# Sheet1.net
KiCad netlist of a schematic drawn in Altium Designer
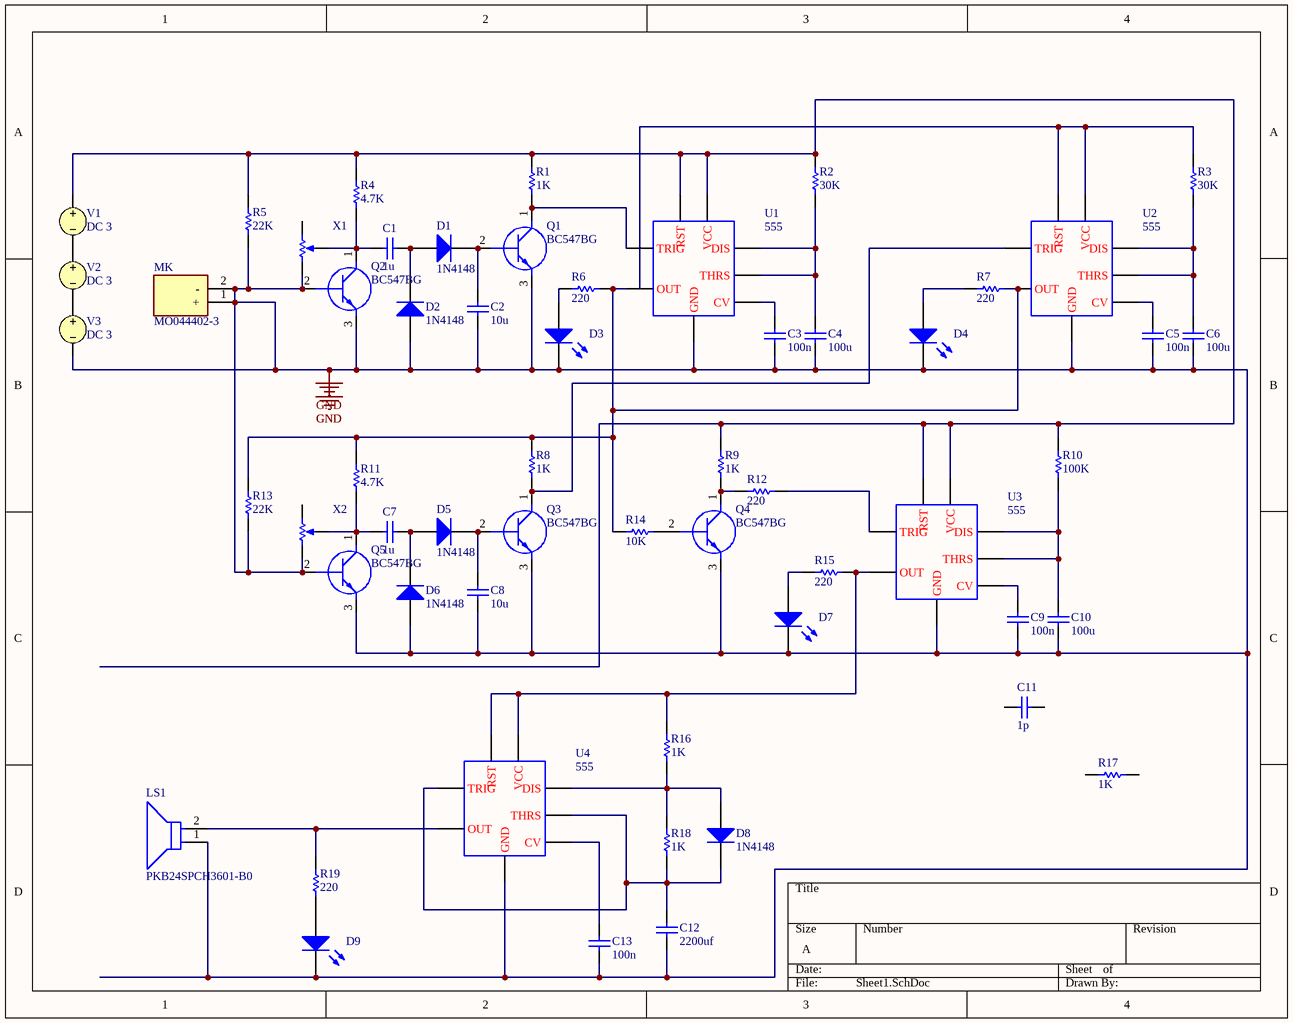
[diagram p0: Sheet1.SchDoc]

(export (version "E")
  (design (tool "Eeschema 10.0.6"))
  (components
    (comp (ref "C1")
      (value "1u")
      (description "Capacitor")
      (libsource (lib "Simulation Generic Components") (part "Capacitor"))
    )
    (comp (ref "C2")
      (value "10u")
      (description "Capacitor")
      (libsource (lib "Simulation Generic Components") (part "Capacitor"))
    )
    (comp (ref "C3")
      (value "100n")
      (description "Capacitor")
      (libsource (lib "Simulation Generic Components") (part "Capacitor"))
    )
    (comp (ref "C4")
      (value "100u")
      (description "Capacitor")
      (libsource (lib "Simulation Generic Components") (part "Capacitor"))
    )
    (comp (ref "C5")
      (value "100n")
      (description "Capacitor")
      (libsource (lib "Simulation Generic Components") (part "Capacitor"))
    )
    (comp (ref "C6")
      (value "100u")
      (description "Capacitor")
      (libsource (lib "Simulation Generic Components") (part "Capacitor"))
    )
    (comp (ref "C7")
      (value "1u")
      (description "Capacitor")
      (libsource (lib "Simulation Generic Components") (part "Capacitor"))
    )
    (comp (ref "C8")
      (value "10u")
      (description "Capacitor")
      (libsource (lib "Simulation Generic Components") (part "Capacitor"))
    )
    (comp (ref "C9")
      (value "100n")
      (description "Capacitor")
      (libsource (lib "Simulation Generic Components") (part "Capacitor"))
    )
    (comp (ref "C10")
      (value "100u")
      (description "Capacitor")
      (libsource (lib "Simulation Generic Components") (part "Capacitor"))
    )
    (comp (ref "C11")
      (value "1p")
      (description "Capacitor")
      (libsource (lib "Simulation Generic Components") (part "Capacitor"))
    )
    (comp (ref "C12")
      (value "2200uf")
      (description "Capacitor")
      (libsource (lib "Simulation Generic Components") (part "Capacitor"))
    )
    (comp (ref "C13")
      (value "100n")
      (description "Capacitor")
      (libsource (lib "Simulation Generic Components") (part "Capacitor"))
    )
    (comp (ref "D1")
      (value "1N4148")
      (footprint "NXP-SOD27-2_V")
      (description "High-speed Diode, 100 V, 450 mA, 2-Pin SOD27, RoHS")
      (fields (field (name "MANUFACTURER") "NXP Semiconductors"))
      (libsource (lib "Altium Content Vault") (part "NXP-A1K2-2"))
    )
    (comp (ref "D2")
      (value "1N4148")
      (footprint "NXP-SOD27-2_V")
      (description "High-speed Diode, 100 V, 450 mA, 2-Pin SOD27, RoHS")
      (fields (field (name "MANUFACTURER") "NXP Semiconductors"))
      (libsource (lib "Altium Content Vault") (part "NXP-A1K2-2"))
    )
    (comp (ref "D3")
      (value "Light-Emitting Diode")
      (libsource (lib "Simulation Generic Components") (part "LED"))
    )
    (comp (ref "D4")
      (value "Light-Emitting Diode")
      (libsource (lib "Simulation Generic Components") (part "LED"))
    )
    (comp (ref "D5")
      (value "1N4148")
      (footprint "NXP-SOD27-2_V")
      (description "High-speed Diode, 100 V, 450 mA, 2-Pin SOD27, RoHS")
      (fields (field (name "MANUFACTURER") "NXP Semiconductors"))
      (libsource (lib "Altium Content Vault") (part "NXP-A1K2-2"))
    )
    (comp (ref "D6")
      (value "1N4148")
      (footprint "NXP-SOD27-2_V")
      (description "High-speed Diode, 100 V, 450 mA, 2-Pin SOD27, RoHS")
      (fields (field (name "MANUFACTURER") "NXP Semiconductors"))
      (libsource (lib "Altium Content Vault") (part "NXP-A1K2-2"))
    )
    (comp (ref "D7")
      (value "Light-Emitting Diode")
      (libsource (lib "Simulation Generic Components") (part "LED"))
    )
    (comp (ref "D8")
      (value "1N4148")
      (footprint "NXP-SOD27-2_V")
      (description "High-speed Diode, 100 V, 450 mA, 2-Pin SOD27, RoHS")
      (fields (field (name "MANUFACTURER") "NXP Semiconductors"))
      (libsource (lib "Altium Content Vault") (part "NXP-A1K2-2"))
    )
    (comp (ref "D9")
      (value "Light-Emitting Diode")
      (libsource (lib "Simulation Generic Components") (part "LED"))
    )
    (comp (ref "LS1")
      (value "PKB24SPCH3601-B0")
      (footprint "FP-PKB24SPCH3601-B0-MFG")
      (description "AUDIO PIEZO TRANSDUCER 3-15V TH")
      (libsource (lib "Altium Content Vault") (part "1973c4b650225fd2ddacaff6b763965"))
    )
    (comp (ref "MK")
      (value "MO044402-3")
      (footprint "SamacSys:MO0444023")
      (description "Microphone")
      (fields (field (name "MOUSER PART NUMBER") "497-MO044402-3"))
      (libsource (lib "*") (part "MO044402-3"))
    )
    (comp (ref "Q1")
      (value "BC547BG")
      (footprint "SamacSys:BC547BG")
      (description "Transistor BJT NPN")
      (libsource (lib "*") (part "BC547BG"))
    )
    (comp (ref "Q2")
      (value "BC547BG")
      (footprint "SamacSys:BC547BG")
      (description "Transistor BJT NPN")
      (libsource (lib "*") (part "BC547BG"))
    )
    (comp (ref "Q3")
      (value "BC547BG")
      (footprint "SamacSys:BC547BG")
      (description "Transistor BJT NPN")
      (libsource (lib "*") (part "BC547BG"))
    )
    (comp (ref "Q4")
      (value "BC547BG")
      (footprint "SamacSys:BC547BG")
      (description "Transistor BJT NPN")
      (libsource (lib "*") (part "BC547BG"))
    )
    (comp (ref "Q5")
      (value "BC547BG")
      (footprint "SamacSys:BC547BG")
      (description "Transistor BJT NPN")
      (libsource (lib "*") (part "BC547BG"))
    )
    (comp (ref "R1")
      (value "1K")
      (description "Resistor")
      (libsource (lib "Simulation Generic Components") (part "Resistor"))
    )
    (comp (ref "R2")
      (value "30K")
      (description "Resistor")
      (libsource (lib "Simulation Generic Components") (part "Resistor"))
    )
    (comp (ref "R3")
      (value "30K")
      (description "Resistor")
      (libsource (lib "Simulation Generic Components") (part "Resistor"))
    )
    (comp (ref "R4")
      (value "4.7K")
      (description "Resistor")
      (libsource (lib "Simulation Generic Components") (part "Resistor"))
    )
    (comp (ref "R5")
      (value "22K")
      (description "Resistor")
      (libsource (lib "Simulation Generic Components") (part "Resistor"))
    )
    (comp (ref "R6")
      (value "220")
      (description "Resistor")
      (libsource (lib "Simulation Generic Components") (part "Resistor"))
    )
    (comp (ref "R7")
      (value "220")
      (description "Resistor")
      (libsource (lib "Simulation Generic Components") (part "Resistor"))
    )
    (comp (ref "R8")
      (value "1K")
      (description "Resistor")
      (libsource (lib "Simulation Generic Components") (part "Resistor"))
    )
    (comp (ref "R9")
      (value "1K")
      (description "Resistor")
      (libsource (lib "Simulation Generic Components") (part "Resistor"))
    )
    (comp (ref "R10")
      (value "100K")
      (description "Resistor")
      (libsource (lib "Simulation Generic Components") (part "Resistor"))
    )
    (comp (ref "R11")
      (value "4.7K")
      (description "Resistor")
      (libsource (lib "Simulation Generic Components") (part "Resistor"))
    )
    (comp (ref "R12")
      (value "220")
      (description "Resistor")
      (libsource (lib "Simulation Generic Components") (part "Resistor"))
    )
    (comp (ref "R13")
      (value "22K")
      (description "Resistor")
      (libsource (lib "Simulation Generic Components") (part "Resistor"))
    )
    (comp (ref "R14")
      (value "10K")
      (description "Resistor")
      (libsource (lib "Simulation Generic Components") (part "Resistor"))
    )
    (comp (ref "R15")
      (value "220")
      (description "Resistor")
      (libsource (lib "Simulation Generic Components") (part "Resistor"))
    )
    (comp (ref "R16")
      (value "1K")
      (description "Resistor")
      (libsource (lib "Simulation Generic Components") (part "Resistor"))
    )
    (comp (ref "R17")
      (value "1K")
      (description "Resistor")
      (libsource (lib "Simulation Generic Components") (part "Resistor"))
    )
    (comp (ref "R18")
      (value "1K")
      (description "Resistor")
      (libsource (lib "Simulation Generic Components") (part "Resistor"))
    )
    (comp (ref "R19")
      (value "220")
      (description "Resistor")
      (libsource (lib "Simulation Generic Components") (part "Resistor"))
    )
    (comp (ref "U1")
      (value "555")
      (description "Timer 555")
      (libsource (lib "Simulation Generic Components") (part "555"))
    )
    (comp (ref "U2")
      (value "555")
      (description "Timer 555")
      (libsource (lib "Simulation Generic Components") (part "555"))
    )
    (comp (ref "U3")
      (value "555")
      (description "Timer 555")
      (libsource (lib "Simulation Generic Components") (part "555"))
    )
    (comp (ref "U4")
      (value "555")
      (description "Timer 555")
      (libsource (lib "Simulation Generic Components") (part "555"))
    )
    (comp (ref "V1")
      (value "DC 3")
      (description "Voltage Source")
      (fields (field (name "PUBLISHER") "Altium Limited"))
      (libsource (lib "Simulation Generic Components") (part "VSRC"))
    )
    (comp (ref "V2")
      (value "DC 3")
      (description "Voltage Source")
      (fields (field (name "PUBLISHER") "Altium Limited"))
      (libsource (lib "Simulation Generic Components") (part "VSRC"))
    )
    (comp (ref "V3")
      (value "DC 3")
      (description "Voltage Source")
      (fields (field (name "PUBLISHER") "Altium Limited"))
      (libsource (lib "Simulation Generic Components") (part "VSRC"))
    )
    (comp (ref "X1")
      (value "Potentiometer")
      (libsource (lib "Simulation Generic Components") (part "Potentiometer"))
    )
    (comp (ref "X2")
      (value "Potentiometer")
      (libsource (lib "Simulation Generic Components") (part "Potentiometer"))
    )
  )
  (nets
    (net (code "1") (name "GND") (class "Default")
      (node (ref "C10") (pin "1") (pinfunction "1_1") (pintype "passive"))
      (node (ref "C12") (pin "1") (pinfunction "1_1") (pintype "passive"))
      (node (ref "C13") (pin "1") (pinfunction "1_1") (pintype "passive"))
      (node (ref "C2") (pin "1") (pinfunction "1_1") (pintype "passive"))
      (node (ref "C3") (pin "1") (pinfunction "1_1") (pintype "passive"))
      (node (ref "C4") (pin "1") (pinfunction "1_1") (pintype "passive"))
      (node (ref "C5") (pin "1") (pinfunction "1_1") (pintype "passive"))
      (node (ref "C6") (pin "1") (pinfunction "1_1") (pintype "passive"))
      (node (ref "C8") (pin "1") (pinfunction "1_1") (pintype "passive"))
      (node (ref "C9") (pin "1") (pinfunction "1_1") (pintype "passive"))
      (node (ref "D2") (pin "1") (pinfunction "A_1") (pintype "passive"))
      (node (ref "D3") (pin "2") (pinfunction "K_2") (pintype "passive"))
      (node (ref "D4") (pin "2") (pinfunction "K_2") (pintype "passive"))
      (node (ref "D6") (pin "1") (pinfunction "A_1") (pintype "passive"))
      (node (ref "D7") (pin "2") (pinfunction "K_2") (pintype "passive"))
      (node (ref "D9") (pin "2") (pinfunction "K_2") (pintype "passive"))
      (node (ref "LS1") (pin "1") (pinfunction "C_1") (pintype "passive"))
      (node (ref "MK") (pin "1") (pinfunction "+_1") (pintype "passive"))
      (node (ref "MK") (pin "2") (pinfunction "-_2") (pintype "passive"))
      (node (ref "Q1") (pin "3") (pinfunction "E_3") (pintype "passive"))
      (node (ref "Q2") (pin "2") (pinfunction "B_2") (pintype "passive"))
      (node (ref "Q2") (pin "3") (pinfunction "E_3") (pintype "passive"))
      (node (ref "Q3") (pin "3") (pinfunction "E_3") (pintype "passive"))
      (node (ref "Q4") (pin "3") (pinfunction "E_3") (pintype "passive"))
      (node (ref "Q5") (pin "2") (pinfunction "B_2") (pintype "passive"))
      (node (ref "Q5") (pin "3") (pinfunction "E_3") (pintype "passive"))
      (node (ref "R13") (pin "1") (pinfunction "1_1") (pintype "passive"))
      (node (ref "R5") (pin "1") (pinfunction "1_1") (pintype "passive"))
      (node (ref "U1") (pin "1") (pinfunction "GND_1") (pintype "passive"))
      (node (ref "U2") (pin "1") (pinfunction "GND_1") (pintype "passive"))
      (node (ref "U3") (pin "1") (pinfunction "GND_1") (pintype "passive"))
      (node (ref "U4") (pin "1") (pinfunction "GND_1") (pintype "passive"))
      (node (ref "V3") (pin "2") (pinfunction "2_2") (pintype "passive"))
      (node (ref "X1") (pin "1") (pinfunction "TOP_1") (pintype "passive"))
      (node (ref "X2") (pin "1") (pinfunction "TOP_1") (pintype "passive"))
    )
    (net (code "2") (name "Net-(D1-A)") (class "Default")
      (node (ref "C1") (pin "2") (pinfunction "2_2") (pintype "passive"))
      (node (ref "D1") (pin "1") (pinfunction "A_1") (pintype "passive"))
      (node (ref "D2") (pin "2") (pinfunction "K_2") (pintype "passive"))
    )
    (net (code "3") (name "Net-(D1-K)") (class "Default")
      (node (ref "C2") (pin "2") (pinfunction "2_2") (pintype "passive"))
      (node (ref "D1") (pin "2") (pinfunction "K_2") (pintype "passive"))
      (node (ref "Q1") (pin "2") (pinfunction "B_2") (pintype "passive"))
    )
    (net (code "4") (name "Net-(D3-A)") (class "Default")
      (node (ref "D3") (pin "1") (pinfunction "A_1") (pintype "passive"))
      (node (ref "R6") (pin "1") (pinfunction "1_1") (pintype "passive"))
    )
    (net (code "5") (name "Net-(D4-A)") (class "Default")
      (node (ref "D4") (pin "1") (pinfunction "A_1") (pintype "passive"))
      (node (ref "R7") (pin "1") (pinfunction "1_1") (pintype "passive"))
    )
    (net (code "6") (name "Net-(D5-A)") (class "Default")
      (node (ref "C7") (pin "2") (pinfunction "2_2") (pintype "passive"))
      (node (ref "D5") (pin "1") (pinfunction "A_1") (pintype "passive"))
      (node (ref "D6") (pin "2") (pinfunction "K_2") (pintype "passive"))
    )
    (net (code "7") (name "Net-(D5-K)") (class "Default")
      (node (ref "C8") (pin "2") (pinfunction "2_2") (pintype "passive"))
      (node (ref "D5") (pin "2") (pinfunction "K_2") (pintype "passive"))
      (node (ref "Q3") (pin "2") (pinfunction "B_2") (pintype "passive"))
    )
    (net (code "8") (name "Net-(D7-A)") (class "Default")
      (node (ref "D7") (pin "1") (pinfunction "A_1") (pintype "passive"))
      (node (ref "R15") (pin "1") (pinfunction "1_1") (pintype "passive"))
    )
    (net (code "9") (name "Net-(D8-A)") (class "Default")
      (node (ref "D8") (pin "1") (pinfunction "A_1") (pintype "passive"))
      (node (ref "R16") (pin "1") (pinfunction "1_1") (pintype "passive"))
      (node (ref "R18") (pin "2") (pinfunction "2_2") (pintype "passive"))
      (node (ref "U4") (pin "7") (pinfunction "DIS_7") (pintype "passive"))
    )
    (net (code "10") (name "Net-(D8-K)") (class "Default")
      (node (ref "C12") (pin "2") (pinfunction "2_2") (pintype "passive"))
      (node (ref "D8") (pin "2") (pinfunction "K_2") (pintype "passive"))
      (node (ref "R18") (pin "1") (pinfunction "1_1") (pintype "passive"))
      (node (ref "U4") (pin "2") (pinfunction "TRIG_2") (pintype "passive"))
      (node (ref "U4") (pin "6") (pinfunction "THRS_6") (pintype "passive"))
    )
    (net (code "11") (name "Net-(D9-A)") (class "Default")
      (node (ref "D9") (pin "1") (pinfunction "A_1") (pintype "passive"))
      (node (ref "R19") (pin "1") (pinfunction "1_1") (pintype "passive"))
    )
    (net (code "12") (name "Net-(LS1-A)") (class "Default")
      (node (ref "LS1") (pin "2") (pinfunction "A_2") (pintype "passive"))
      (node (ref "R19") (pin "2") (pinfunction "2_2") (pintype "passive"))
      (node (ref "U4") (pin "3") (pinfunction "OUT_3") (pintype "passive"))
    )
    (net (code "13") (name "Net-(Q1-C)") (class "Default")
      (node (ref "Q1") (pin "1") (pinfunction "C_1") (pintype "passive"))
      (node (ref "R1") (pin "1") (pinfunction "1_1") (pintype "passive"))
      (node (ref "U1") (pin "2") (pinfunction "TRIG_2") (pintype "passive"))
    )
    (net (code "14") (name "Net-(Q2-C)") (class "Default")
      (node (ref "C1") (pin "1") (pinfunction "1_1") (pintype "passive"))
      (node (ref "Q2") (pin "1") (pinfunction "C_1") (pintype "passive"))
      (node (ref "R4") (pin "1") (pinfunction "1_1") (pintype "passive"))
      (node (ref "X1") (pin "3") (pinfunction "TAP_3") (pintype "passive"))
    )
    (net (code "15") (name "Net-(Q3-C)") (class "Default")
      (node (ref "Q3") (pin "1") (pinfunction "C_1") (pintype "passive"))
      (node (ref "R8") (pin "1") (pinfunction "1_1") (pintype "passive"))
      (node (ref "U2") (pin "2") (pinfunction "TRIG_2") (pintype "passive"))
    )
    (net (code "16") (name "Net-(Q4-B)") (class "Default")
      (node (ref "Q4") (pin "2") (pinfunction "B_2") (pintype "passive"))
      (node (ref "R14") (pin "2") (pinfunction "2_2") (pintype "passive"))
    )
    (net (code "17") (name "Net-(Q4-C)") (class "Default")
      (node (ref "Q4") (pin "1") (pinfunction "C_1") (pintype "passive"))
      (node (ref "R12") (pin "1") (pinfunction "1_1") (pintype "passive"))
      (node (ref "R9") (pin "1") (pinfunction "1_1") (pintype "passive"))
    )
    (net (code "18") (name "Net-(Q5-C)") (class "Default")
      (node (ref "C7") (pin "1") (pinfunction "1_1") (pintype "passive"))
      (node (ref "Q5") (pin "1") (pinfunction "C_1") (pintype "passive"))
      (node (ref "R11") (pin "1") (pinfunction "1_1") (pintype "passive"))
      (node (ref "X2") (pin "3") (pinfunction "TAP_3") (pintype "passive"))
    )
    (net (code "19") (name "Net-(U1-CV)") (class "Default")
      (node (ref "C3") (pin "2") (pinfunction "2_2") (pintype "passive"))
      (node (ref "U1") (pin "5") (pinfunction "CV_5") (pintype "passive"))
    )
    (net (code "20") (name "Net-(U1-DIS)") (class "Default")
      (node (ref "C4") (pin "2") (pinfunction "2_2") (pintype "passive"))
      (node (ref "R2") (pin "1") (pinfunction "1_1") (pintype "passive"))
      (node (ref "U1") (pin "6") (pinfunction "THRS_6") (pintype "passive"))
      (node (ref "U1") (pin "7") (pinfunction "DIS_7") (pintype "passive"))
    )
    (net (code "21") (name "Net-(U1-OUT)") (class "Default")
      (node (ref "R11") (pin "2") (pinfunction "2_2") (pintype "passive"))
      (node (ref "R13") (pin "2") (pinfunction "2_2") (pintype "passive"))
      (node (ref "R14") (pin "1") (pinfunction "1_1") (pintype "passive"))
      (node (ref "R6") (pin "2") (pinfunction "2_2") (pintype "passive"))
      (node (ref "R7") (pin "2") (pinfunction "2_2") (pintype "passive"))
      (node (ref "R8") (pin "2") (pinfunction "2_2") (pintype "passive"))
      (node (ref "U1") (pin "3") (pinfunction "OUT_3") (pintype "passive"))
      (node (ref "U2") (pin "3") (pinfunction "OUT_3") (pintype "passive"))
    )
    (net (code "22") (name "Net-(U1-RST)") (class "Default")
      (node (ref "R1") (pin "2") (pinfunction "2_2") (pintype "passive"))
      (node (ref "R10") (pin "2") (pinfunction "2_2") (pintype "passive"))
      (node (ref "R2") (pin "2") (pinfunction "2_2") (pintype "passive"))
      (node (ref "R4") (pin "2") (pinfunction "2_2") (pintype "passive"))
      (node (ref "R5") (pin "2") (pinfunction "2_2") (pintype "passive"))
      (node (ref "R9") (pin "2") (pinfunction "2_2") (pintype "passive"))
      (node (ref "U1") (pin "4") (pinfunction "RST_4") (pintype "passive"))
      (node (ref "U1") (pin "8") (pinfunction "VCC_8") (pintype "passive"))
      (node (ref "U3") (pin "4") (pinfunction "RST_4") (pintype "passive"))
      (node (ref "U3") (pin "8") (pinfunction "VCC_8") (pintype "passive"))
      (node (ref "V1") (pin "1") (pinfunction "1_1") (pintype "passive"))
    )
    (net (code "23") (name "Net-(U2-CV)") (class "Default")
      (node (ref "C5") (pin "2") (pinfunction "2_2") (pintype "passive"))
      (node (ref "U2") (pin "5") (pinfunction "CV_5") (pintype "passive"))
    )
    (net (code "24") (name "Net-(U2-DIS)") (class "Default")
      (node (ref "C6") (pin "2") (pinfunction "2_2") (pintype "passive"))
      (node (ref "R3") (pin "1") (pinfunction "1_1") (pintype "passive"))
      (node (ref "U2") (pin "6") (pinfunction "THRS_6") (pintype "passive"))
      (node (ref "U2") (pin "7") (pinfunction "DIS_7") (pintype "passive"))
    )
    (net (code "25") (name "Net-(U2-RST)") (class "Default")
      (node (ref "R3") (pin "2") (pinfunction "2_2") (pintype "passive"))
      (node (ref "U2") (pin "4") (pinfunction "RST_4") (pintype "passive"))
      (node (ref "U2") (pin "8") (pinfunction "VCC_8") (pintype "passive"))
    )
    (net (code "26") (name "Net-(U3-CV)") (class "Default")
      (node (ref "C9") (pin "2") (pinfunction "2_2") (pintype "passive"))
      (node (ref "U3") (pin "5") (pinfunction "CV_5") (pintype "passive"))
    )
    (net (code "27") (name "Net-(U3-DIS)") (class "Default")
      (node (ref "C10") (pin "2") (pinfunction "2_2") (pintype "passive"))
      (node (ref "R10") (pin "1") (pinfunction "1_1") (pintype "passive"))
      (node (ref "U3") (pin "6") (pinfunction "THRS_6") (pintype "passive"))
      (node (ref "U3") (pin "7") (pinfunction "DIS_7") (pintype "passive"))
    )
    (net (code "28") (name "Net-(U3-OUT)") (class "Default")
      (node (ref "R15") (pin "2") (pinfunction "2_2") (pintype "passive"))
      (node (ref "R16") (pin "2") (pinfunction "2_2") (pintype "passive"))
      (node (ref "U3") (pin "3") (pinfunction "OUT_3") (pintype "passive"))
      (node (ref "U4") (pin "4") (pinfunction "RST_4") (pintype "passive"))
      (node (ref "U4") (pin "8") (pinfunction "VCC_8") (pintype "passive"))
    )
    (net (code "29") (name "Net-(U3-TRIG)") (class "Default")
      (node (ref "R12") (pin "2") (pinfunction "2_2") (pintype "passive"))
      (node (ref "U3") (pin "2") (pinfunction "TRIG_2") (pintype "passive"))
    )
    (net (code "30") (name "Net-(U4-CV)") (class "Default")
      (node (ref "C13") (pin "2") (pinfunction "2_2") (pintype "passive"))
      (node (ref "U4") (pin "5") (pinfunction "CV_5") (pintype "passive"))
    )
    (net (code "31") (name "Net-(V1-Pad2)") (class "Default")
      (node (ref "V1") (pin "2") (pinfunction "2_2") (pintype "passive"))
      (node (ref "V2") (pin "1") (pinfunction "1_1") (pintype "passive"))
    )
    (net (code "32") (name "Net-(V2-Pad2)") (class "Default")
      (node (ref "V2") (pin "2") (pinfunction "2_2") (pintype "passive"))
      (node (ref "V3") (pin "1") (pinfunction "1_1") (pintype "passive"))
    )
    (net (code "33") (name "unconnected-(C11-Pad1)") (class "Default")
      (node (ref "C11") (pin "1") (pinfunction "1_1") (pintype "passive"))
    )
    (net (code "34") (name "unconnected-(C11-Pad2)") (class "Default")
      (node (ref "C11") (pin "2") (pinfunction "2_2") (pintype "passive"))
    )
    (net (code "35") (name "unconnected-(R17-Pad1)") (class "Default")
      (node (ref "R17") (pin "1") (pinfunction "1_1") (pintype "passive"))
    )
    (net (code "36") (name "unconnected-(R17-Pad2)") (class "Default")
      (node (ref "R17") (pin "2") (pinfunction "2_2") (pintype "passive"))
    )
    (net (code "37") (name "unconnected-(X1-BOT-Pad2)") (class "Default")
      (node (ref "X1") (pin "2") (pinfunction "BOT_2") (pintype "passive"))
    )
    (net (code "38") (name "unconnected-(X2-BOT-Pad2)") (class "Default")
      (node (ref "X2") (pin "2") (pinfunction "BOT_2") (pintype "passive"))
    )
  )
)
